# al115v20_relays.net
KiCad netlist of a schematic drawn in Altium Designer
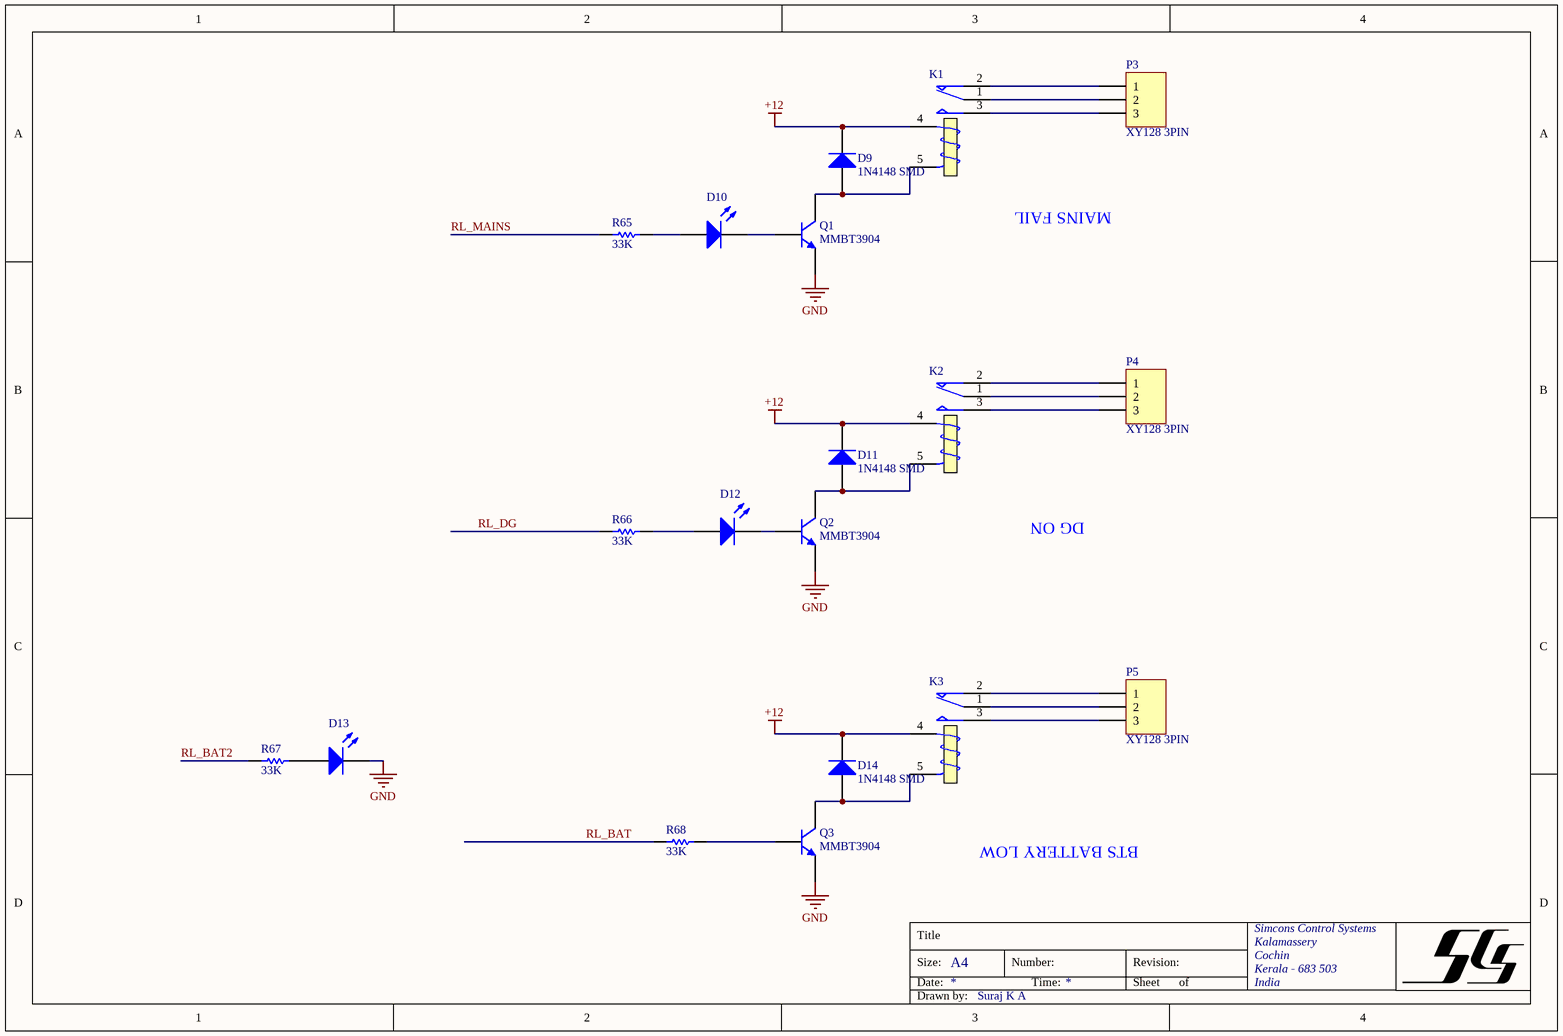
[diagram p0: al115v20_relays.SchDoc]

(export (version "E")
  (design (tool "Eeschema 10.0.6"))
  (components
    (comp (ref "D9")
      (value "1N4148 SMD")
      (footprint "4148SMDW")
      (description "Default Diode")
      (fields (field (name "PUBLISHER") "Altium Limited"))
      (libsource (lib "Miscellaneous Devices") (part "Diode"))
    )
    (comp (ref "D10")
      (value "LED R/R 5MM")
      (footprint "LEDSMALL")
      (description "Typical RED GaAs LED")
      (fields (field (name "PUBLISHER") "Altium Limited"))
      (libsource (lib "Miscellaneous Devices") (part "LED1"))
    )
    (comp (ref "D11")
      (value "1N4148 SMD")
      (footprint "4148SMDW")
      (description "Default Diode")
      (fields (field (name "PUBLISHER") "Altium Limited"))
      (libsource (lib "Miscellaneous Devices") (part "Diode"))
    )
    (comp (ref "D12")
      (value "LED R/R 5MM")
      (footprint "LEDSMALL")
      (description "Typical RED GaAs LED")
      (fields (field (name "PUBLISHER") "Altium Limited"))
      (libsource (lib "Miscellaneous Devices") (part "LED1"))
    )
    (comp (ref "D13")
      (value "LED R/R 5MM")
      (footprint "LEDSMALL")
      (description "Typical RED GaAs LED")
      (fields (field (name "PUBLISHER") "Altium Limited"))
      (libsource (lib "Miscellaneous Devices") (part "LED1"))
    )
    (comp (ref "D14")
      (value "1N4148 SMD")
      (footprint "4148SMDW")
      (description "Default Diode")
      (fields (field (name "PUBLISHER") "Altium Limited"))
      (libsource (lib "Miscellaneous Devices") (part "Diode"))
    )
    (comp (ref "K1")
      (value "Relay")
      (footprint "RELAY")
      (description "SPDT Relay")
      (fields (field (name "PUBLISHER") "Altium Limited"))
      (libsource (lib "Miscellaneous Devices") (part "Relay"))
    )
    (comp (ref "K2")
      (value "Relay")
      (footprint "RELAY")
      (description "SPDT Relay")
      (fields (field (name "PUBLISHER") "Altium Limited"))
      (libsource (lib "Miscellaneous Devices") (part "Relay"))
    )
    (comp (ref "K3")
      (value "Relay")
      (footprint "RELAY")
      (description "SPDT Relay")
      (fields (field (name "PUBLISHER") "Altium Limited"))
      (libsource (lib "Miscellaneous Devices") (part "Relay"))
    )
    (comp (ref "P3")
      (value "XY128 3PIN")
      (footprint "XY128_5.08_3PIN")
      (description "Header, 3-Pin")
      (fields (field (name "PUBLISHER") "Altium Limited"))
      (libsource (lib "Miscellaneous Connectors") (part "Header 3"))
    )
    (comp (ref "P4")
      (value "XY128 3PIN")
      (footprint "XY128_5.08_3PIN")
      (description "Header, 3-Pin")
      (fields (field (name "PUBLISHER") "Altium Limited"))
      (libsource (lib "Miscellaneous Connectors") (part "Header 3"))
    )
    (comp (ref "P5")
      (value "XY128 3PIN")
      (footprint "XY128_5.08_3PIN")
      (description "Header, 3-Pin")
      (fields (field (name "PUBLISHER") "Altium Limited"))
      (libsource (lib "Miscellaneous Connectors") (part "Header 3"))
    )
    (comp (ref "Q1")
      (value "MMBT3904")
      (footprint "SOT23_M")
      (description "NPN General-purpose Transistor")
      (fields (field (name "PUBLISHER") "Altium Limited"))
      (libsource (lib "Philips Discrete BJT - Low Power") (part "BC847"))
    )
    (comp (ref "Q2")
      (value "MMBT3904")
      (footprint "SOT23_M")
      (description "NPN General-purpose Transistor")
      (fields (field (name "PUBLISHER") "Altium Limited"))
      (libsource (lib "Philips Discrete BJT - Low Power") (part "BC847"))
    )
    (comp (ref "Q3")
      (value "MMBT3904")
      (footprint "SOT23_M")
      (description "NPN General-purpose Transistor")
      (fields (field (name "PUBLISHER") "Altium Limited"))
      (libsource (lib "Philips Discrete BJT - Low Power") (part "BC847"))
    )
    (comp (ref "R65")
      (value "33K")
      (footprint "R1206")
      (description "Semiconductor Resistor")
      (fields (field (name "Comment") "330E 1206") (field (name "PUBLISHER") "Altium Limited"))
      (libsource (lib "Miscellaneous Devices") (part "Res Semi"))
    )
    (comp (ref "R66")
      (value "33K")
      (footprint "R1206")
      (description "Semiconductor Resistor")
      (fields (field (name "Comment") "330E 1206") (field (name "PUBLISHER") "Altium Limited"))
      (libsource (lib "Miscellaneous Devices") (part "Res Semi"))
    )
    (comp (ref "R67")
      (value "33K")
      (footprint "R1206")
      (description "Semiconductor Resistor")
      (fields (field (name "Comment") "330E 1206") (field (name "PUBLISHER") "Altium Limited"))
      (libsource (lib "Miscellaneous Devices") (part "Res Semi"))
    )
    (comp (ref "R68")
      (value "33K")
      (footprint "R1206")
      (description "Semiconductor Resistor")
      (fields (field (name "Comment") "4.7K 1206") (field (name "PUBLISHER") "Altium Limited"))
      (libsource (lib "Miscellaneous Devices") (part "Res Semi"))
    )
  )
  (nets
    (net (code "1") (name "+12") (class "Default")
      (node (ref "D11") (pin "2") (pinfunction "K_2") (pintype "passive"))
      (node (ref "D14") (pin "2") (pinfunction "K_2") (pintype "passive"))
      (node (ref "D9") (pin "2") (pinfunction "K_2") (pintype "passive"))
      (node (ref "K1") (pin "4") (pinfunction "T1_4") (pintype "passive"))
      (node (ref "K2") (pin "4") (pinfunction "T1_4") (pintype "passive"))
      (node (ref "K3") (pin "4") (pinfunction "T1_4") (pintype "passive"))
    )
    (net (code "2") (name "/RL_BAT") (class "Default")
      (node (ref "R68") (pin "2") (pinfunction "2_2") (pintype "passive"))
    )
    (net (code "3") (name "/RL_BAT2") (class "Default")
      (node (ref "R67") (pin "1") (pinfunction "1_1") (pintype "passive"))
    )
    (net (code "4") (name "/RL_DG") (class "Default")
      (node (ref "R66") (pin "2") (pinfunction "2_2") (pintype "passive"))
    )
    (net (code "5") (name "/RL_MAINS") (class "Default")
      (node (ref "R65") (pin "2") (pinfunction "2_2") (pintype "passive"))
    )
    (net (code "6") (name "GND") (class "Default")
      (node (ref "D13") (pin "2") (pinfunction "K_2") (pintype "passive"))
      (node (ref "Q1") (pin "2") (pinfunction "E_2") (pintype "passive"))
      (node (ref "Q2") (pin "2") (pinfunction "E_2") (pintype "passive"))
      (node (ref "Q3") (pin "2") (pinfunction "E_2") (pintype "passive"))
    )
    (net (code "7") (name "Net-(D9-A)") (class "Default")
      (node (ref "D9") (pin "1") (pinfunction "A_1") (pintype "passive"))
      (node (ref "K1") (pin "5") (pinfunction "T2_5") (pintype "passive"))
      (node (ref "Q1") (pin "3") (pinfunction "C_3") (pintype "passive"))
    )
    (net (code "8") (name "Net-(D10-A)") (class "Default")
      (node (ref "D10") (pin "1") (pinfunction "A_1") (pintype "passive"))
      (node (ref "R65") (pin "1") (pinfunction "1_1") (pintype "passive"))
    )
    (net (code "9") (name "Net-(D10-K)") (class "Default")
      (node (ref "D10") (pin "2") (pinfunction "K_2") (pintype "passive"))
      (node (ref "Q1") (pin "1") (pinfunction "B_1") (pintype "passive"))
    )
    (net (code "10") (name "Net-(D11-A)") (class "Default")
      (node (ref "D11") (pin "1") (pinfunction "A_1") (pintype "passive"))
      (node (ref "K2") (pin "5") (pinfunction "T2_5") (pintype "passive"))
      (node (ref "Q2") (pin "3") (pinfunction "C_3") (pintype "passive"))
    )
    (net (code "11") (name "Net-(D12-A)") (class "Default")
      (node (ref "D12") (pin "1") (pinfunction "A_1") (pintype "passive"))
      (node (ref "R66") (pin "1") (pinfunction "1_1") (pintype "passive"))
    )
    (net (code "12") (name "Net-(D12-K)") (class "Default")
      (node (ref "D12") (pin "2") (pinfunction "K_2") (pintype "passive"))
      (node (ref "Q2") (pin "1") (pinfunction "B_1") (pintype "passive"))
    )
    (net (code "13") (name "Net-(D13-A)") (class "Default")
      (node (ref "D13") (pin "1") (pinfunction "A_1") (pintype "passive"))
      (node (ref "R67") (pin "2") (pinfunction "2_2") (pintype "passive"))
    )
    (net (code "14") (name "Net-(D14-A)") (class "Default")
      (node (ref "D14") (pin "1") (pinfunction "A_1") (pintype "passive"))
      (node (ref "K3") (pin "5") (pinfunction "T2_5") (pintype "passive"))
      (node (ref "Q3") (pin "3") (pinfunction "C_3") (pintype "passive"))
    )
    (net (code "15") (name "Net-(K1-COM)") (class "Default")
      (node (ref "K1") (pin "1") (pinfunction "COM_1") (pintype "passive"))
      (node (ref "P3") (pin "2") (pinfunction "2_2") (pintype "passive"))
    )
    (net (code "16") (name "Net-(K1-NC)") (class "Default")
      (node (ref "K1") (pin "2") (pinfunction "NC_2") (pintype "passive"))
      (node (ref "P3") (pin "1") (pinfunction "1_1") (pintype "passive"))
    )
    (net (code "17") (name "Net-(K1-NO)") (class "Default")
      (node (ref "K1") (pin "3") (pinfunction "NO_3") (pintype "passive"))
      (node (ref "P3") (pin "3") (pinfunction "3_3") (pintype "passive"))
    )
    (net (code "18") (name "Net-(K2-COM)") (class "Default")
      (node (ref "K2") (pin "1") (pinfunction "COM_1") (pintype "passive"))
      (node (ref "P4") (pin "2") (pinfunction "2_2") (pintype "passive"))
    )
    (net (code "19") (name "Net-(K2-NC)") (class "Default")
      (node (ref "K2") (pin "2") (pinfunction "NC_2") (pintype "passive"))
      (node (ref "P4") (pin "1") (pinfunction "1_1") (pintype "passive"))
    )
    (net (code "20") (name "Net-(K2-NO)") (class "Default")
      (node (ref "K2") (pin "3") (pinfunction "NO_3") (pintype "passive"))
      (node (ref "P4") (pin "3") (pinfunction "3_3") (pintype "passive"))
    )
    (net (code "21") (name "Net-(K3-COM)") (class "Default")
      (node (ref "K3") (pin "1") (pinfunction "COM_1") (pintype "passive"))
      (node (ref "P5") (pin "2") (pinfunction "2_2") (pintype "passive"))
    )
    (net (code "22") (name "Net-(K3-NC)") (class "Default")
      (node (ref "K3") (pin "2") (pinfunction "NC_2") (pintype "passive"))
      (node (ref "P5") (pin "1") (pinfunction "1_1") (pintype "passive"))
    )
    (net (code "23") (name "Net-(K3-NO)") (class "Default")
      (node (ref "K3") (pin "3") (pinfunction "NO_3") (pintype "passive"))
      (node (ref "P5") (pin "3") (pinfunction "3_3") (pintype "passive"))
    )
    (net (code "24") (name "Net-(Q3-B)") (class "Default")
      (node (ref "Q3") (pin "1") (pinfunction "B_1") (pintype "passive"))
      (node (ref "R68") (pin "1") (pinfunction "1_1") (pintype "passive"))
    )
  )
)
